# LED.net
KiCad netlist of a schematic drawn in Altium Designer
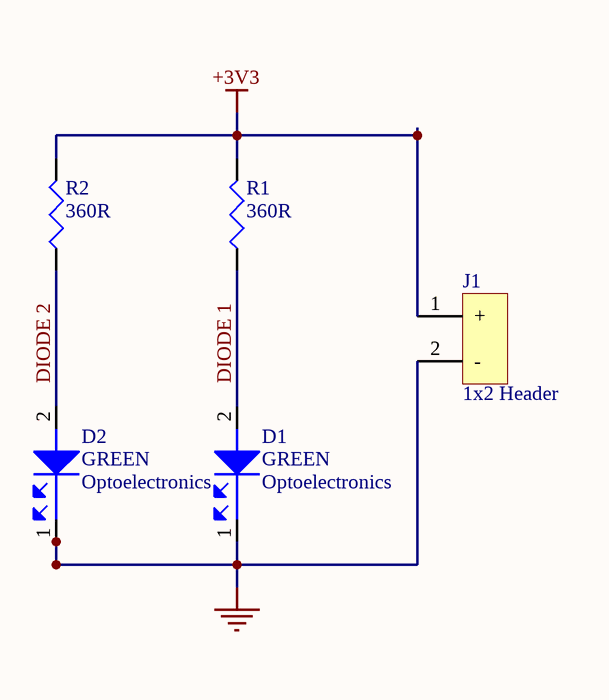
[diagram p0: LED.SchDoc]

(export (version "E")
  (design (tool "Eeschema 10.0.6"))
  (components
    (comp (ref "D1")
      (value "GREEN")
      (footprint "LED0603G")
      (description "LED GREEN ESS II SMD")
      (fields
        (field (name "MANUFACTURER") "Panasonic SSG")
        (field (name "MANUFACTURER PART NUMBER") "LNJ337W83RA")
        (field (name "CATEGORY") "Optoelectronics")
      )
      (libsource (lib "LED_SchLib") (part "LNJ337W83RA"))
    )
    (comp (ref "D2")
      (value "GREEN")
      (footprint "LED0603G")
      (description "LED GREEN ESS II SMD")
      (fields
        (field (name "MANUFACTURER") "Panasonic SSG")
        (field (name "MANUFACTURER PART NUMBER") "LNJ337W83RA")
        (field (name "CATEGORY") "Optoelectronics")
      )
      (libsource (lib "LED_SchLib") (part "LNJ337W83RA"))
    )
    (comp (ref "J1")
      (value "1x2 Header")
      (footprint "HDR1X2")
      (description "Conn Wire to Board HDR 2 POS 2.54mm Solder ST Thru-Hole Bag")
      (fields (field (name "MANUFACTURER") "Molex") (field (name "MANUFACTURER PART NUMBER") "22-29-2021"))
      (libsource (lib "LED_SchLib") (part "22-29-2021"))
    )
    (comp (ref "R1")
      (value "360R")
      (footprint "R0805")
      (description "RES SMD 360 OHM 1% 1/8W 0805")
      (fields
        (field (name "MANUFACTURER") "Vishay")
        (field (name "MANUFACTURER PART NUMBER") "CRCW0805360RFKEA")
      )
      (libsource (lib "LED_SchLib") (part "CRCW0805360RFKEA"))
    )
    (comp (ref "R2")
      (value "360R")
      (footprint "R0805")
      (description "RES SMD 360 OHM 1% 1/8W 0805")
      (fields
        (field (name "MANUFACTURER") "Vishay")
        (field (name "MANUFACTURER PART NUMBER") "CRCW0805360RFKEA")
      )
      (libsource (lib "LED_SchLib") (part "CRCW0805360RFKEA"))
    )
  )
  (nets
    (net (code "1") (name "+3V3") (class "Default")
      (node (ref "J1") (pin "1") (pinfunction "+_1") (pintype "passive"))
      (node (ref "R1") (pin "2") (pinfunction "2_2") (pintype "passive"))
      (node (ref "R2") (pin "2") (pinfunction "2_2") (pintype "passive"))
    )
    (net (code "2") (name "/DIODE 1") (class "Default")
      (node (ref "D1") (pin "2") (pinfunction "2_2") (pintype "passive"))
      (node (ref "R1") (pin "1") (pinfunction "1_1") (pintype "passive"))
    )
    (net (code "3") (name "/DIODE 2") (class "Default")
      (node (ref "D2") (pin "2") (pinfunction "2_2") (pintype "passive"))
      (node (ref "R2") (pin "1") (pinfunction "1_1") (pintype "passive"))
    )
    (net (code "4") (name "GND") (class "Default")
      (node (ref "D1") (pin "1") (pinfunction "1_1") (pintype "passive"))
      (node (ref "D2") (pin "1") (pinfunction "1_1") (pintype "passive"))
      (node (ref "J1") (pin "2") (pinfunction "-_2") (pintype "passive"))
    )
  )
)
